# BOC_DAUGHTER.net
KiCad netlist of a schematic drawn in Altium Designer
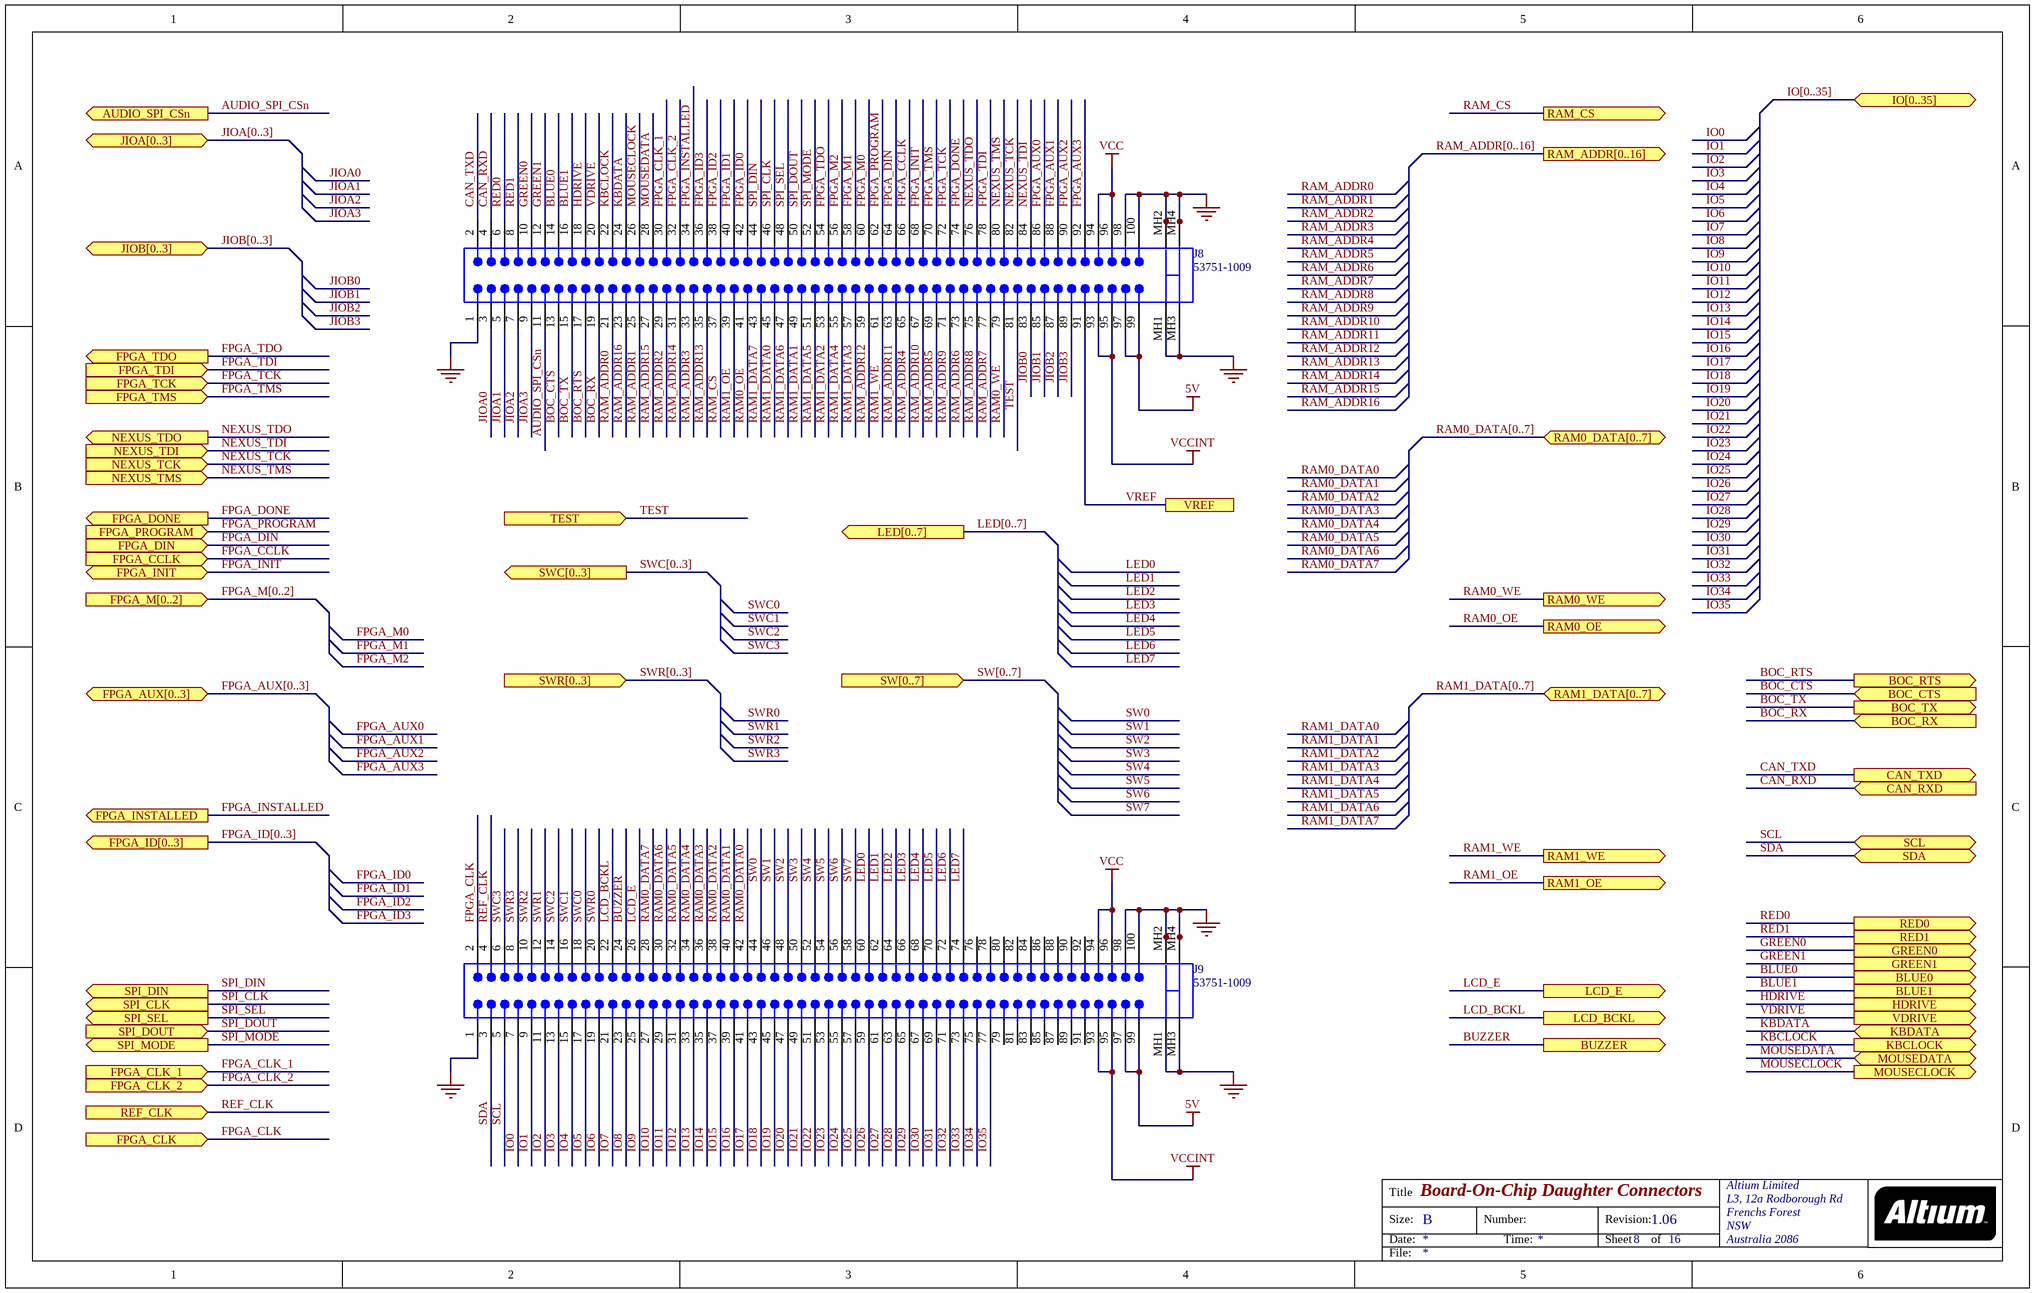
[diagram p0: BOC_DAUGHTER.SchDoc]

(export (version "E")
  (design (tool "Eeschema 10.0.6"))
  (components
    (comp (ref "J8")
      (value "53751-1009")
      (footprint "Altium Nanoboard Project:53751")
      (fields
        (field (name "MANUFACTURER") "Molex")
        (field (name "VOLTAGE") "100V")
        (field (name "PUBLISHER") "Altium Limited")
      )
      (libsource (lib "Altium Nanoboard Project") (part "53751-1009"))
    )
    (comp (ref "J9")
      (value "53751-1009")
      (footprint "Altium Nanoboard Project:53751")
      (fields
        (field (name "MANUFACTURER") "Molex")
        (field (name "VOLTAGE") "100V")
        (field (name "PUBLISHER") "Altium Limited")
      )
      (libsource (lib "Altium Nanoboard Project") (part "53751-1009"))
    )
  )
  (nets
    (net (code "1") (name "/AUDIO_SPI_CSn") (class "Default")
      (node (ref "J8") (pin "11") (pinfunction "11_11") (pintype "passive"))
    )
    (net (code "2") (name "/BLUE0") (class "Default")
      (node (ref "J8") (pin "14") (pinfunction "14_14") (pintype "passive"))
    )
    (net (code "3") (name "/BLUE1") (class "Default")
      (node (ref "J8") (pin "16") (pinfunction "16_16") (pintype "passive"))
    )
    (net (code "4") (name "/BOC_CTS") (class "Default")
      (node (ref "J8") (pin "13") (pinfunction "13_13") (pintype "passive"))
    )
    (net (code "5") (name "/BOC_RTS") (class "Default")
      (node (ref "J8") (pin "17") (pinfunction "17_17") (pintype "passive"))
    )
    (net (code "6") (name "/BOC_RX") (class "Default")
      (node (ref "J8") (pin "19") (pinfunction "19_19") (pintype "passive"))
    )
    (net (code "7") (name "/BOC_TX") (class "Default")
      (node (ref "J8") (pin "15") (pinfunction "15_15") (pintype "passive"))
    )
    (net (code "8") (name "/BUZZER") (class "Default")
      (node (ref "J9") (pin "24") (pinfunction "24_24") (pintype "passive"))
    )
    (net (code "9") (name "/CAN_RXD") (class "Default")
      (node (ref "J8") (pin "4") (pinfunction "4_4") (pintype "passive"))
    )
    (net (code "10") (name "/CAN_TXD") (class "Default")
      (node (ref "J8") (pin "2") (pinfunction "2_2") (pintype "passive"))
    )
    (net (code "11") (name "/FPGA_AUX0") (class "Default")
      (node (ref "J8") (pin "86") (pinfunction "86_86") (pintype "passive"))
    )
    (net (code "12") (name "/FPGA_AUX1") (class "Default")
      (node (ref "J8") (pin "88") (pinfunction "88_88") (pintype "passive"))
    )
    (net (code "13") (name "/FPGA_AUX2") (class "Default")
      (node (ref "J8") (pin "90") (pinfunction "90_90") (pintype "passive"))
    )
    (net (code "14") (name "/FPGA_AUX3") (class "Default")
      (node (ref "J8") (pin "92") (pinfunction "92_92") (pintype "passive"))
    )
    (net (code "16") (name "/FPGA_CCLK") (class "Default")
      (node (ref "J8") (pin "66") (pinfunction "66_66") (pintype "passive"))
    )
    (net (code "17") (name "/FPGA_CLK") (class "Default")
      (node (ref "J9") (pin "2") (pinfunction "2_2") (pintype "passive"))
    )
    (net (code "18") (name "/FPGA_CLK_1") (class "Default")
      (node (ref "J8") (pin "30") (pinfunction "30_30") (pintype "passive"))
    )
    (net (code "19") (name "/FPGA_CLK_2") (class "Default")
      (node (ref "J8") (pin "32") (pinfunction "32_32") (pintype "passive"))
    )
    (net (code "20") (name "/FPGA_DIN") (class "Default")
      (node (ref "J8") (pin "64") (pinfunction "64_64") (pintype "passive"))
    )
    (net (code "21") (name "/FPGA_DONE") (class "Default")
      (node (ref "J8") (pin "74") (pinfunction "74_74") (pintype "passive"))
    )
    (net (code "22") (name "/FPGA_ID0") (class "Default")
      (node (ref "J8") (pin "42") (pinfunction "42_42") (pintype "passive"))
    )
    (net (code "23") (name "/FPGA_ID1") (class "Default")
      (node (ref "J8") (pin "40") (pinfunction "40_40") (pintype "passive"))
    )
    (net (code "24") (name "/FPGA_ID2") (class "Default")
      (node (ref "J8") (pin "38") (pinfunction "38_38") (pintype "passive"))
    )
    (net (code "25") (name "/FPGA_ID3") (class "Default")
      (node (ref "J8") (pin "36") (pinfunction "36_36") (pintype "passive"))
    )
    (net (code "27") (name "/FPGA_INIT") (class "Default")
      (node (ref "J8") (pin "68") (pinfunction "68_68") (pintype "passive"))
    )
    (net (code "28") (name "/FPGA_INSTALLED") (class "Default")
      (node (ref "J8") (pin "34") (pinfunction "34_34") (pintype "passive"))
    )
    (net (code "29") (name "/FPGA_M0") (class "Default")
      (node (ref "J8") (pin "60") (pinfunction "60_60") (pintype "passive"))
    )
    (net (code "30") (name "/FPGA_M1") (class "Default")
      (node (ref "J8") (pin "58") (pinfunction "58_58") (pintype "passive"))
    )
    (net (code "31") (name "/FPGA_M2") (class "Default")
      (node (ref "J8") (pin "56") (pinfunction "56_56") (pintype "passive"))
    )
    (net (code "33") (name "/FPGA_PROGRAM") (class "Default")
      (node (ref "J8") (pin "62") (pinfunction "62_62") (pintype "passive"))
    )
    (net (code "34") (name "/FPGA_TCK") (class "Default")
      (node (ref "J8") (pin "72") (pinfunction "72_72") (pintype "passive"))
    )
    (net (code "35") (name "/FPGA_TDI") (class "Default")
      (node (ref "J8") (pin "78") (pinfunction "78_78") (pintype "passive"))
    )
    (net (code "36") (name "/FPGA_TDO") (class "Default")
      (node (ref "J8") (pin "54") (pinfunction "54_54") (pintype "passive"))
    )
    (net (code "37") (name "/FPGA_TMS") (class "Default")
      (node (ref "J8") (pin "70") (pinfunction "70_70") (pintype "passive"))
    )
    (net (code "38") (name "/GREEN0") (class "Default")
      (node (ref "J8") (pin "10") (pinfunction "10_10") (pintype "passive"))
    )
    (net (code "39") (name "/GREEN1") (class "Default")
      (node (ref "J8") (pin "12") (pinfunction "12_12") (pintype "passive"))
    )
    (net (code "40") (name "/HDRIVE") (class "Default")
      (node (ref "J8") (pin "18") (pinfunction "18_18") (pintype "passive"))
    )
    (net (code "41") (name "/IO0") (class "Default")
      (node (ref "J9") (pin "7") (pinfunction "7_7") (pintype "passive"))
    )
    (net (code "42") (name "/IO1") (class "Default")
      (node (ref "J9") (pin "9") (pinfunction "9_9") (pintype "passive"))
    )
    (net (code "43") (name "/IO2") (class "Default")
      (node (ref "J9") (pin "11") (pinfunction "11_11") (pintype "passive"))
    )
    (net (code "44") (name "/IO3") (class "Default")
      (node (ref "J9") (pin "13") (pinfunction "13_13") (pintype "passive"))
    )
    (net (code "45") (name "/IO4") (class "Default")
      (node (ref "J9") (pin "15") (pinfunction "15_15") (pintype "passive"))
    )
    (net (code "46") (name "/IO5") (class "Default")
      (node (ref "J9") (pin "17") (pinfunction "17_17") (pintype "passive"))
    )
    (net (code "47") (name "/IO6") (class "Default")
      (node (ref "J9") (pin "19") (pinfunction "19_19") (pintype "passive"))
    )
    (net (code "48") (name "/IO7") (class "Default")
      (node (ref "J9") (pin "21") (pinfunction "21_21") (pintype "passive"))
    )
    (net (code "49") (name "/IO8") (class "Default")
      (node (ref "J9") (pin "23") (pinfunction "23_23") (pintype "passive"))
    )
    (net (code "50") (name "/IO9") (class "Default")
      (node (ref "J9") (pin "25") (pinfunction "25_25") (pintype "passive"))
    )
    (net (code "51") (name "/IO10") (class "Default")
      (node (ref "J9") (pin "27") (pinfunction "27_27") (pintype "passive"))
    )
    (net (code "52") (name "/IO11") (class "Default")
      (node (ref "J9") (pin "29") (pinfunction "29_29") (pintype "passive"))
    )
    (net (code "53") (name "/IO12") (class "Default")
      (node (ref "J9") (pin "31") (pinfunction "31_31") (pintype "passive"))
    )
    (net (code "54") (name "/IO13") (class "Default")
      (node (ref "J9") (pin "33") (pinfunction "33_33") (pintype "passive"))
    )
    (net (code "55") (name "/IO14") (class "Default")
      (node (ref "J9") (pin "35") (pinfunction "35_35") (pintype "passive"))
    )
    (net (code "56") (name "/IO15") (class "Default")
      (node (ref "J9") (pin "37") (pinfunction "37_37") (pintype "passive"))
    )
    (net (code "57") (name "/IO16") (class "Default")
      (node (ref "J9") (pin "39") (pinfunction "39_39") (pintype "passive"))
    )
    (net (code "58") (name "/IO17") (class "Default")
      (node (ref "J9") (pin "41") (pinfunction "41_41") (pintype "passive"))
    )
    (net (code "59") (name "/IO18") (class "Default")
      (node (ref "J9") (pin "43") (pinfunction "43_43") (pintype "passive"))
    )
    (net (code "60") (name "/IO19") (class "Default")
      (node (ref "J9") (pin "45") (pinfunction "45_45") (pintype "passive"))
    )
    (net (code "61") (name "/IO20") (class "Default")
      (node (ref "J9") (pin "47") (pinfunction "47_47") (pintype "passive"))
    )
    (net (code "62") (name "/IO21") (class "Default")
      (node (ref "J9") (pin "49") (pinfunction "49_49") (pintype "passive"))
    )
    (net (code "63") (name "/IO22") (class "Default")
      (node (ref "J9") (pin "51") (pinfunction "51_51") (pintype "passive"))
    )
    (net (code "64") (name "/IO23") (class "Default")
      (node (ref "J9") (pin "53") (pinfunction "53_53") (pintype "passive"))
    )
    (net (code "65") (name "/IO24") (class "Default")
      (node (ref "J9") (pin "55") (pinfunction "55_55") (pintype "passive"))
    )
    (net (code "66") (name "/IO25") (class "Default")
      (node (ref "J9") (pin "57") (pinfunction "57_57") (pintype "passive"))
    )
    (net (code "67") (name "/IO26") (class "Default")
      (node (ref "J9") (pin "59") (pinfunction "59_59") (pintype "passive"))
    )
    (net (code "68") (name "/IO27") (class "Default")
      (node (ref "J9") (pin "61") (pinfunction "61_61") (pintype "passive"))
    )
    (net (code "69") (name "/IO28") (class "Default")
      (node (ref "J9") (pin "63") (pinfunction "63_63") (pintype "passive"))
    )
    (net (code "70") (name "/IO29") (class "Default")
      (node (ref "J9") (pin "65") (pinfunction "65_65") (pintype "passive"))
    )
    (net (code "71") (name "/IO30") (class "Default")
      (node (ref "J9") (pin "67") (pinfunction "67_67") (pintype "passive"))
    )
    (net (code "72") (name "/IO31") (class "Default")
      (node (ref "J9") (pin "69") (pinfunction "69_69") (pintype "passive"))
    )
    (net (code "73") (name "/IO32") (class "Default")
      (node (ref "J9") (pin "71") (pinfunction "71_71") (pintype "passive"))
    )
    (net (code "74") (name "/IO33") (class "Default")
      (node (ref "J9") (pin "73") (pinfunction "73_73") (pintype "passive"))
    )
    (net (code "75") (name "/IO34") (class "Default")
      (node (ref "J9") (pin "75") (pinfunction "75_75") (pintype "passive"))
    )
    (net (code "76") (name "/IO35") (class "Default")
      (node (ref "J9") (pin "77") (pinfunction "77_77") (pintype "passive"))
    )
    (net (code "78") (name "/JIOA0") (class "Default")
      (node (ref "J8") (pin "3") (pinfunction "3_3") (pintype "passive"))
    )
    (net (code "79") (name "/JIOA1") (class "Default")
      (node (ref "J8") (pin "5") (pinfunction "5_5") (pintype "passive"))
    )
    (net (code "80") (name "/JIOA2") (class "Default")
      (node (ref "J8") (pin "7") (pinfunction "7_7") (pintype "passive"))
    )
    (net (code "81") (name "/JIOA3") (class "Default")
      (node (ref "J8") (pin "9") (pinfunction "9_9") (pintype "passive"))
    )
    (net (code "83") (name "/JIOB0") (class "Default")
      (node (ref "J8") (pin "83") (pinfunction "83_83") (pintype "passive"))
    )
    (net (code "84") (name "/JIOB1") (class "Default")
      (node (ref "J8") (pin "85") (pinfunction "85_85") (pintype "passive"))
    )
    (net (code "85") (name "/JIOB2") (class "Default")
      (node (ref "J8") (pin "87") (pinfunction "87_87") (pintype "passive"))
    )
    (net (code "86") (name "/JIOB3") (class "Default")
      (node (ref "J8") (pin "89") (pinfunction "89_89") (pintype "passive"))
    )
    (net (code "88") (name "/KBCLOCK") (class "Default")
      (node (ref "J8") (pin "22") (pinfunction "22_22") (pintype "passive"))
    )
    (net (code "89") (name "/KBDATA") (class "Default")
      (node (ref "J8") (pin "24") (pinfunction "24_24") (pintype "passive"))
    )
    (net (code "90") (name "/LCD_BCKL") (class "Default")
      (node (ref "J9") (pin "22") (pinfunction "22_22") (pintype "passive"))
    )
    (net (code "91") (name "/LCD_E") (class "Default")
      (node (ref "J9") (pin "26") (pinfunction "26_26") (pintype "passive"))
    )
    (net (code "92") (name "/LED0") (class "Default")
      (node (ref "J9") (pin "60") (pinfunction "60_60") (pintype "passive"))
    )
    (net (code "93") (name "/LED1") (class "Default")
      (node (ref "J9") (pin "62") (pinfunction "62_62") (pintype "passive"))
    )
    (net (code "94") (name "/LED2") (class "Default")
      (node (ref "J9") (pin "64") (pinfunction "64_64") (pintype "passive"))
    )
    (net (code "95") (name "/LED3") (class "Default")
      (node (ref "J9") (pin "66") (pinfunction "66_66") (pintype "passive"))
    )
    (net (code "96") (name "/LED4") (class "Default")
      (node (ref "J9") (pin "68") (pinfunction "68_68") (pintype "passive"))
    )
    (net (code "97") (name "/LED5") (class "Default")
      (node (ref "J9") (pin "70") (pinfunction "70_70") (pintype "passive"))
    )
    (net (code "98") (name "/LED6") (class "Default")
      (node (ref "J9") (pin "72") (pinfunction "72_72") (pintype "passive"))
    )
    (net (code "99") (name "/LED7") (class "Default")
      (node (ref "J9") (pin "74") (pinfunction "74_74") (pintype "passive"))
    )
    (net (code "101") (name "/MOUSECLOCK") (class "Default")
      (node (ref "J8") (pin "26") (pinfunction "26_26") (pintype "passive"))
    )
    (net (code "102") (name "/MOUSEDATA") (class "Default")
      (node (ref "J8") (pin "28") (pinfunction "28_28") (pintype "passive"))
    )
    (net (code "103") (name "/NEXUS_TCK") (class "Default")
      (node (ref "J8") (pin "82") (pinfunction "82_82") (pintype "passive"))
    )
    (net (code "104") (name "/NEXUS_TDI") (class "Default")
      (node (ref "J8") (pin "84") (pinfunction "84_84") (pintype "passive"))
    )
    (net (code "105") (name "/NEXUS_TDO") (class "Default")
      (node (ref "J8") (pin "76") (pinfunction "76_76") (pintype "passive"))
    )
    (net (code "106") (name "/NEXUS_TMS") (class "Default")
      (node (ref "J8") (pin "80") (pinfunction "80_80") (pintype "passive"))
    )
    (net (code "107") (name "/RAM0_DATA0") (class "Default")
      (node (ref "J9") (pin "42") (pinfunction "42_42") (pintype "passive"))
    )
    (net (code "108") (name "/RAM0_DATA1") (class "Default")
      (node (ref "J9") (pin "40") (pinfunction "40_40") (pintype "passive"))
    )
    (net (code "109") (name "/RAM0_DATA2") (class "Default")
      (node (ref "J9") (pin "38") (pinfunction "38_38") (pintype "passive"))
    )
    (net (code "110") (name "/RAM0_DATA3") (class "Default")
      (node (ref "J9") (pin "36") (pinfunction "36_36") (pintype "passive"))
    )
    (net (code "111") (name "/RAM0_DATA4") (class "Default")
      (node (ref "J9") (pin "34") (pinfunction "34_34") (pintype "passive"))
    )
    (net (code "112") (name "/RAM0_DATA5") (class "Default")
      (node (ref "J9") (pin "32") (pinfunction "32_32") (pintype "passive"))
    )
    (net (code "113") (name "/RAM0_DATA6") (class "Default")
      (node (ref "J9") (pin "30") (pinfunction "30_30") (pintype "passive"))
    )
    (net (code "114") (name "/RAM0_DATA7") (class "Default")
      (node (ref "J9") (pin "28") (pinfunction "28_28") (pintype "passive"))
    )
    (net (code "116") (name "/RAM0_OE") (class "Default")
      (node (ref "J8") (pin "41") (pinfunction "41_41") (pintype "passive"))
    )
    (net (code "117") (name "/RAM0_WE") (class "Default")
      (node (ref "J8") (pin "79") (pinfunction "79_79") (pintype "passive"))
    )
    (net (code "118") (name "/RAM1_DATA0") (class "Default")
      (node (ref "J8") (pin "45") (pinfunction "45_45") (pintype "passive"))
    )
    (net (code "119") (name "/RAM1_DATA1") (class "Default")
      (node (ref "J8") (pin "49") (pinfunction "49_49") (pintype "passive"))
    )
    (net (code "120") (name "/RAM1_DATA2") (class "Default")
      (node (ref "J8") (pin "53") (pinfunction "53_53") (pintype "passive"))
    )
    (net (code "121") (name "/RAM1_DATA3") (class "Default")
      (node (ref "J8") (pin "57") (pinfunction "57_57") (pintype "passive"))
    )
    (net (code "122") (name "/RAM1_DATA4") (class "Default")
      (node (ref "J8") (pin "55") (pinfunction "55_55") (pintype "passive"))
    )
    (net (code "123") (name "/RAM1_DATA5") (class "Default")
      (node (ref "J8") (pin "51") (pinfunction "51_51") (pintype "passive"))
    )
    (net (code "124") (name "/RAM1_DATA6") (class "Default")
      (node (ref "J8") (pin "47") (pinfunction "47_47") (pintype "passive"))
    )
    (net (code "125") (name "/RAM1_DATA7") (class "Default")
      (node (ref "J8") (pin "43") (pinfunction "43_43") (pintype "passive"))
    )
    (net (code "127") (name "/RAM1_OE") (class "Default")
      (node (ref "J8") (pin "39") (pinfunction "39_39") (pintype "passive"))
    )
    (net (code "128") (name "/RAM1_WE") (class "Default")
      (node (ref "J8") (pin "61") (pinfunction "61_61") (pintype "passive"))
    )
    (net (code "129") (name "/RAM_ADDR0") (class "Default")
      (node (ref "J8") (pin "21") (pinfunction "21_21") (pintype "passive"))
    )
    (net (code "130") (name "/RAM_ADDR1") (class "Default")
      (node (ref "J8") (pin "25") (pinfunction "25_25") (pintype "passive"))
    )
    (net (code "131") (name "/RAM_ADDR2") (class "Default")
      (node (ref "J8") (pin "29") (pinfunction "29_29") (pintype "passive"))
    )
    (net (code "132") (name "/RAM_ADDR3") (class "Default")
      (node (ref "J8") (pin "33") (pinfunction "33_33") (pintype "passive"))
    )
    (net (code "133") (name "/RAM_ADDR4") (class "Default")
      (node (ref "J8") (pin "65") (pinfunction "65_65") (pintype "passive"))
    )
    (net (code "134") (name "/RAM_ADDR5") (class "Default")
      (node (ref "J8") (pin "69") (pinfunction "69_69") (pintype "passive"))
    )
    (net (code "135") (name "/RAM_ADDR6") (class "Default")
      (node (ref "J8") (pin "73") (pinfunction "73_73") (pintype "passive"))
    )
    (net (code "136") (name "/RAM_ADDR7") (class "Default")
      (node (ref "J8") (pin "77") (pinfunction "77_77") (pintype "passive"))
    )
    (net (code "137") (name "/RAM_ADDR8") (class "Default")
      (node (ref "J8") (pin "75") (pinfunction "75_75") (pintype "passive"))
    )
    (net (code "138") (name "/RAM_ADDR9") (class "Default")
      (node (ref "J8") (pin "71") (pinfunction "71_71") (pintype "passive"))
    )
    (net (code "139") (name "/RAM_ADDR10") (class "Default")
      (node (ref "J8") (pin "67") (pinfunction "67_67") (pintype "passive"))
    )
    (net (code "140") (name "/RAM_ADDR11") (class "Default")
      (node (ref "J8") (pin "63") (pinfunction "63_63") (pintype "passive"))
    )
    (net (code "141") (name "/RAM_ADDR12") (class "Default")
      (node (ref "J8") (pin "59") (pinfunction "59_59") (pintype "passive"))
    )
    (net (code "142") (name "/RAM_ADDR13") (class "Default")
      (node (ref "J8") (pin "35") (pinfunction "35_35") (pintype "passive"))
    )
    (net (code "143") (name "/RAM_ADDR14") (class "Default")
      (node (ref "J8") (pin "31") (pinfunction "31_31") (pintype "passive"))
    )
    (net (code "144") (name "/RAM_ADDR15") (class "Default")
      (node (ref "J8") (pin "27") (pinfunction "27_27") (pintype "passive"))
    )
    (net (code "145") (name "/RAM_ADDR16") (class "Default")
      (node (ref "J8") (pin "23") (pinfunction "23_23") (pintype "passive"))
    )
    (net (code "147") (name "/RAM_CS") (class "Default")
      (node (ref "J8") (pin "37") (pinfunction "37_37") (pintype "passive"))
    )
    (net (code "148") (name "/RED0") (class "Default")
      (node (ref "J8") (pin "6") (pinfunction "6_6") (pintype "passive"))
    )
    (net (code "149") (name "/RED1") (class "Default")
      (node (ref "J8") (pin "8") (pinfunction "8_8") (pintype "passive"))
    )
    (net (code "150") (name "/REF_CLK") (class "Default")
      (node (ref "J9") (pin "4") (pinfunction "4_4") (pintype "passive"))
    )
    (net (code "151") (name "/SCL") (class "Default")
      (node (ref "J9") (pin "5") (pinfunction "5_5") (pintype "passive"))
    )
    (net (code "152") (name "/SDA") (class "Default")
      (node (ref "J9") (pin "3") (pinfunction "3_3") (pintype "passive"))
    )
    (net (code "153") (name "/SPI_CLK") (class "Default")
      (node (ref "J8") (pin "46") (pinfunction "46_46") (pintype "passive"))
    )
    (net (code "154") (name "/SPI_DIN") (class "Default")
      (node (ref "J8") (pin "44") (pinfunction "44_44") (pintype "passive"))
    )
    (net (code "155") (name "/SPI_DOUT") (class "Default")
      (node (ref "J8") (pin "50") (pinfunction "50_50") (pintype "passive"))
    )
    (net (code "156") (name "/SPI_MODE") (class "Default")
      (node (ref "J8") (pin "52") (pinfunction "52_52") (pintype "passive"))
    )
    (net (code "157") (name "/SPI_SEL") (class "Default")
      (node (ref "J8") (pin "48") (pinfunction "48_48") (pintype "passive"))
    )
    (net (code "158") (name "/SW0") (class "Default")
      (node (ref "J9") (pin "44") (pinfunction "44_44") (pintype "passive"))
    )
    (net (code "159") (name "/SW1") (class "Default")
      (node (ref "J9") (pin "46") (pinfunction "46_46") (pintype "passive"))
    )
    (net (code "160") (name "/SW2") (class "Default")
      (node (ref "J9") (pin "48") (pinfunction "48_48") (pintype "passive"))
    )
    (net (code "161") (name "/SW3") (class "Default")
      (node (ref "J9") (pin "50") (pinfunction "50_50") (pintype "passive"))
    )
    (net (code "162") (name "/SW4") (class "Default")
      (node (ref "J9") (pin "52") (pinfunction "52_52") (pintype "passive"))
    )
    (net (code "163") (name "/SW5") (class "Default")
      (node (ref "J9") (pin "54") (pinfunction "54_54") (pintype "passive"))
    )
    (net (code "164") (name "/SW6") (class "Default")
      (node (ref "J9") (pin "56") (pinfunction "56_56") (pintype "passive"))
    )
    (net (code "165") (name "/SW7") (class "Default")
      (node (ref "J9") (pin "58") (pinfunction "58_58") (pintype "passive"))
    )
    (net (code "166") (name "/SWC0") (class "Default")
      (node (ref "J9") (pin "18") (pinfunction "18_18") (pintype "passive"))
    )
    (net (code "167") (name "/SWC1") (class "Default")
      (node (ref "J9") (pin "16") (pinfunction "16_16") (pintype "passive"))
    )
    (net (code "168") (name "/SWC2") (class "Default")
      (node (ref "J9") (pin "14") (pinfunction "14_14") (pintype "passive"))
    )
    (net (code "169") (name "/SWC3") (class "Default")
      (node (ref "J9") (pin "6") (pinfunction "6_6") (pintype "passive"))
    )
    (net (code "171") (name "/SWR0") (class "Default")
      (node (ref "J9") (pin "20") (pinfunction "20_20") (pintype "passive"))
    )
    (net (code "172") (name "/SWR1") (class "Default")
      (node (ref "J9") (pin "12") (pinfunction "12_12") (pintype "passive"))
    )
    (net (code "173") (name "/SWR2") (class "Default")
      (node (ref "J9") (pin "10") (pinfunction "10_10") (pintype "passive"))
    )
    (net (code "174") (name "/SWR3") (class "Default")
      (node (ref "J9") (pin "8") (pinfunction "8_8") (pintype "passive"))
    )
    (net (code "177") (name "/TEST") (class "Default")
      (node (ref "J8") (pin "81") (pinfunction "81_81") (pintype "passive"))
    )
    (net (code "178") (name "/VDRIVE") (class "Default")
      (node (ref "J8") (pin "20") (pinfunction "20_20") (pintype "passive"))
    )
    (net (code "179") (name "/VREF") (class "Default")
      (node (ref "J8") (pin "91") (pinfunction "91_91") (pintype "passive"))
    )
    (net (code "180") (name "5V") (class "Default")
      (node (ref "J8") (pin "97") (pinfunction "97_97") (pintype "passive"))
      (node (ref "J8") (pin "99") (pinfunction "99_99") (pintype "passive"))
      (node (ref "J9") (pin "97") (pinfunction "97_97") (pintype "passive"))
      (node (ref "J9") (pin "99") (pinfunction "99_99") (pintype "passive"))
    )
    (net (code "181") (name "GND") (class "Default")
      (node (ref "J8") (pin "1") (pinfunction "1_1") (pintype "passive"))
      (node (ref "J8") (pin "100") (pinfunction "100_100") (pintype "passive"))
      (node (ref "J8") (pin "98") (pinfunction "98_98") (pintype "passive"))
      (node (ref "J8") (pin "MH1") (pinfunction "MH1_MH1") (pintype "passive"))
      (node (ref "J8") (pin "MH2") (pinfunction "MH2_MH2") (pintype "passive"))
      (node (ref "J8") (pin "MH2A") (pinfunction "MH2A_MH2A") (pintype "passive"))
      (node (ref "J8") (pin "MH2B") (pinfunction "MH2B_MH2B") (pintype "passive"))
      (node (ref "J8") (pin "MH3") (pinfunction "MH3_MH3") (pintype "passive"))
      (node (ref "J8") (pin "MH4") (pinfunction "MH4_MH4") (pintype "passive"))
      (node (ref "J8") (pin "MH4A") (pinfunction "MH4A_MH4A") (pintype "passive"))
      (node (ref "J8") (pin "MH4B") (pinfunction "MH4B_MH4B") (pintype "passive"))
      (node (ref "J9") (pin "1") (pinfunction "1_1") (pintype "passive"))
      (node (ref "J9") (pin "100") (pinfunction "100_100") (pintype "passive"))
      (node (ref "J9") (pin "98") (pinfunction "98_98") (pintype "passive"))
      (node (ref "J9") (pin "MH1") (pinfunction "MH1_MH1") (pintype "passive"))
      (node (ref "J9") (pin "MH2") (pinfunction "MH2_MH2") (pintype "passive"))
      (node (ref "J9") (pin "MH2A") (pinfunction "MH2A_MH2A") (pintype "passive"))
      (node (ref "J9") (pin "MH2B") (pinfunction "MH2B_MH2B") (pintype "passive"))
      (node (ref "J9") (pin "MH3") (pinfunction "MH3_MH3") (pintype "passive"))
      (node (ref "J9") (pin "MH4") (pinfunction "MH4_MH4") (pintype "passive"))
      (node (ref "J9") (pin "MH4A") (pinfunction "MH4A_MH4A") (pintype "passive"))
      (node (ref "J9") (pin "MH4B") (pinfunction "MH4B_MH4B") (pintype "passive"))
    )
    (net (code "182") (name "VCC") (class "Default")
      (node (ref "J8") (pin "94") (pinfunction "94_94") (pintype "passive"))
      (node (ref "J8") (pin "96") (pinfunction "96_96") (pintype "passive"))
      (node (ref "J9") (pin "94") (pinfunction "94_94") (pintype "passive"))
      (node (ref "J9") (pin "96") (pinfunction "96_96") (pintype "passive"))
    )
    (net (code "183") (name "VCCINT") (class "Default")
      (node (ref "J8") (pin "93") (pinfunction "93_93") (pintype "passive"))
      (node (ref "J8") (pin "95") (pinfunction "95_95") (pintype "passive"))
      (node (ref "J9") (pin "93") (pinfunction "93_93") (pintype "passive"))
      (node (ref "J9") (pin "95") (pinfunction "95_95") (pintype "passive"))
    )
    (net (code "184") (name "unconnected-(J9-Pad76)") (class "Default")
      (node (ref "J9") (pin "76") (pinfunction "76_76") (pintype "passive"))
    )
    (net (code "185") (name "unconnected-(J9-Pad78)") (class "Default")
      (node (ref "J9") (pin "78") (pinfunction "78_78") (pintype "passive"))
    )
    (net (code "186") (name "unconnected-(J9-Pad79)") (class "Default")
      (node (ref "J9") (pin "79") (pinfunction "79_79") (pintype "passive"))
    )
    (net (code "187") (name "unconnected-(J9-Pad80)") (class "Default")
      (node (ref "J9") (pin "80") (pinfunction "80_80") (pintype "passive"))
    )
    (net (code "188") (name "unconnected-(J9-Pad81)") (class "Default")
      (node (ref "J9") (pin "81") (pinfunction "81_81") (pintype "passive"))
    )
    (net (code "189") (name "unconnected-(J9-Pad82)") (class "Default")
      (node (ref "J9") (pin "82") (pinfunction "82_82") (pintype "passive"))
    )
    (net (code "190") (name "unconnected-(J9-Pad83)") (class "Default")
      (node (ref "J9") (pin "83") (pinfunction "83_83") (pintype "passive"))
    )
    (net (code "191") (name "unconnected-(J9-Pad84)") (class "Default")
      (node (ref "J9") (pin "84") (pinfunction "84_84") (pintype "passive"))
    )
    (net (code "192") (name "unconnected-(J9-Pad85)") (class "Default")
      (node (ref "J9") (pin "85") (pinfunction "85_85") (pintype "passive"))
    )
    (net (code "193") (name "unconnected-(J9-Pad86)") (class "Default")
      (node (ref "J9") (pin "86") (pinfunction "86_86") (pintype "passive"))
    )
    (net (code "194") (name "unconnected-(J9-Pad87)") (class "Default")
      (node (ref "J9") (pin "87") (pinfunction "87_87") (pintype "passive"))
    )
    (net (code "195") (name "unconnected-(J9-Pad88)") (class "Default")
      (node (ref "J9") (pin "88") (pinfunction "88_88") (pintype "passive"))
    )
    (net (code "196") (name "unconnected-(J9-Pad89)") (class "Default")
      (node (ref "J9") (pin "89") (pinfunction "89_89") (pintype "passive"))
    )
    (net (code "197") (name "unconnected-(J9-Pad90)") (class "Default")
      (node (ref "J9") (pin "90") (pinfunction "90_90") (pintype "passive"))
    )
    (net (code "198") (name "unconnected-(J9-Pad91)") (class "Default")
      (node (ref "J9") (pin "91") (pinfunction "91_91") (pintype "passive"))
    )
    (net (code "199") (name "unconnected-(J9-Pad92)") (class "Default")
      (node (ref "J9") (pin "92") (pinfunction "92_92") (pintype "passive"))
    )
  )
)
